# Sheet1.net
KiCad netlist of a schematic drawn in Altium Designer
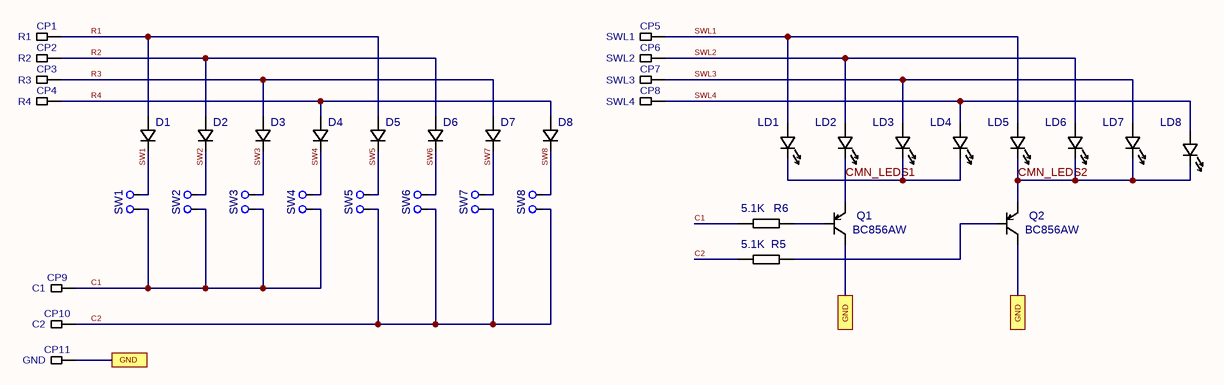
[diagram p0: Sheet1.SCHDOC]

(export (version "E")
  (design (tool "Eeschema 10.0.6"))
  (components
    (comp (ref "CP1")
      (value "R1")
      (footprint "PAD_RRX60Y60D0T")
      (description "PAD_RRX60Y60D0T")
      (libsource (lib "*") (part "PAD_RRX60Y60D0T"))
    )
    (comp (ref "CP2")
      (value "R2")
      (footprint "PAD_RRX60Y60D0T")
      (description "PAD_RRX60Y60D0T")
      (libsource (lib "*") (part "PAD_RRX60Y60D0T"))
    )
    (comp (ref "CP3")
      (value "R3")
      (footprint "PAD_RRX60Y60D0T")
      (description "PAD_RRX60Y60D0T")
      (libsource (lib "*") (part "PAD_RRX60Y60D0T"))
    )
    (comp (ref "CP4")
      (value "R4")
      (footprint "PAD_RRX60Y60D0T")
      (description "PAD_RRX60Y60D0T")
      (libsource (lib "*") (part "PAD_RRX60Y60D0T"))
    )
    (comp (ref "CP5")
      (value "SWL1")
      (footprint "PAD_RRX60Y60D0T")
      (description "PAD_RRX60Y60D0T")
      (libsource (lib "*") (part "PAD_RRX60Y60D0T"))
    )
    (comp (ref "CP6")
      (value "SWL2")
      (footprint "PAD_RRX60Y60D0T")
      (description "PAD_RRX60Y60D0T")
      (libsource (lib "*") (part "PAD_RRX60Y60D0T"))
    )
    (comp (ref "CP7")
      (value "SWL3")
      (footprint "PAD_RRX60Y60D0T")
      (description "PAD_RRX60Y60D0T")
      (libsource (lib "*") (part "PAD_RRX60Y60D0T"))
    )
    (comp (ref "CP8")
      (value "SWL4")
      (footprint "PAD_RRX60Y60D0T")
      (description "PAD_RRX60Y60D0T")
      (libsource (lib "*") (part "PAD_RRX60Y60D0T"))
    )
    (comp (ref "CP9")
      (value "C1")
      (footprint "PAD_RRX60Y60D0T")
      (description "PAD_RRX60Y60D0T")
      (libsource (lib "*") (part "PAD_RRX60Y60D0T"))
    )
    (comp (ref "CP10")
      (value "C2")
      (footprint "PAD_RRX60Y60D0T")
      (description "PAD_RRX60Y60D0T")
      (libsource (lib "*") (part "PAD_RRX60Y60D0T"))
    )
    (comp (ref "CP11")
      (value "GND")
      (footprint "PAD_RRX60Y60D0T")
      (description "PAD_RRX60Y60D0T")
      (libsource (lib "*") (part "PAD_RRX60Y60D0T"))
    )
    (comp (ref "D1") (value "1N4148") (footprint "SOD80") (libsource (lib "*") (part "1N4148")))
    (comp (ref "D2") (value "1N4148") (footprint "SOD80") (libsource (lib "*") (part "1N4148")))
    (comp (ref "D3") (value "1N4148") (footprint "SOD80") (libsource (lib "*") (part "1N4148")))
    (comp (ref "D4") (value "1N4148") (footprint "SOD80") (libsource (lib "*") (part "1N4148")))
    (comp (ref "D5") (value "1N4148") (footprint "SOD80") (libsource (lib "*") (part "1N4148")))
    (comp (ref "D6") (value "1N4148") (footprint "SOD80") (libsource (lib "*") (part "1N4148")))
    (comp (ref "D7") (value "1N4148") (footprint "SOD80") (libsource (lib "*") (part "1N4148")))
    (comp (ref "D8") (value "1N4148") (footprint "SOD80") (libsource (lib "*") (part "1N4148")))
    (comp (ref "LD1") (value "LED_3MM") (footprint "LED_3MM_DIP") (libsource (lib "*") (part "LED_3MM")))
    (comp (ref "LD2") (value "LED_3MM") (footprint "LED_3MM_DIP") (libsource (lib "*") (part "LED_3MM")))
    (comp (ref "LD3") (value "LED_3MM") (footprint "LED_3MM_DIP") (libsource (lib "*") (part "LED_3MM")))
    (comp (ref "LD4") (value "LED_3MM") (footprint "LED_3MM_DIP") (libsource (lib "*") (part "LED_3MM")))
    (comp (ref "LD5") (value "LED_3MM") (footprint "LED_3MM_DIP") (libsource (lib "*") (part "LED_3MM")))
    (comp (ref "LD6") (value "LED_3MM") (footprint "LED_3MM_DIP") (libsource (lib "*") (part "LED_3MM")))
    (comp (ref "LD7") (value "LED_3MM") (footprint "LED_3MM_DIP") (libsource (lib "*") (part "LED_3MM")))
    (comp (ref "LD8") (value "LED_3MM") (footprint "LED_3MM_DIP") (libsource (lib "*") (part "LED_3MM")))
    (comp (ref "Q1") (value "BC856AW") (footprint "SOT23") (libsource (lib "*") (part "BC856AW")))
    (comp (ref "Q2") (value "BC856AW") (footprint "SOT23") (libsource (lib "*") (part "BC856AW")))
    (comp (ref "R5")
      (value "5.1K")
      (footprint "R0805")
      (description "RES_SMD_0805")
      (libsource (lib "*") (part "RES_SMD_0805"))
    )
    (comp (ref "R6")
      (value "5.1K")
      (footprint "R0805")
      (description "RES_SMD_0805")
      (libsource (lib "*") (part "RES_SMD_0805"))
    )
    (comp (ref "SW1")
      (value "2P:EX60Y60D0T-CD100")
      (footprint "2P:EX60Y60D0T-CD100")
      (libsource (lib "*") (part "2P{colon}EX60Y60D0T-CD100"))
    )
    (comp (ref "SW2")
      (value "2P:EX60Y60D0T-CD100")
      (footprint "2P:EX60Y60D0T-CD100")
      (libsource (lib "*") (part "2P{colon}EX60Y60D0T-CD100"))
    )
    (comp (ref "SW3")
      (value "2P:EX60Y60D0T-CD100")
      (footprint "2P:EX60Y60D0T-CD100")
      (libsource (lib "*") (part "2P{colon}EX60Y60D0T-CD100"))
    )
    (comp (ref "SW4")
      (value "2P:EX60Y60D0T-CD100")
      (footprint "2P:EX60Y60D0T-CD100")
      (libsource (lib "*") (part "2P{colon}EX60Y60D0T-CD100"))
    )
    (comp (ref "SW5")
      (value "2P:EX60Y60D0T-CD100")
      (footprint "2P:EX60Y60D0T-CD100")
      (libsource (lib "*") (part "2P{colon}EX60Y60D0T-CD100"))
    )
    (comp (ref "SW6")
      (value "2P:EX60Y60D0T-CD100")
      (footprint "2P:EX60Y60D0T-CD100")
      (libsource (lib "*") (part "2P{colon}EX60Y60D0T-CD100"))
    )
    (comp (ref "SW7")
      (value "2P:EX60Y60D0T-CD100")
      (footprint "2P:EX60Y60D0T-CD100")
      (libsource (lib "*") (part "2P{colon}EX60Y60D0T-CD100"))
    )
    (comp (ref "SW8")
      (value "2P:EX60Y60D0T-CD100")
      (footprint "2P:EX60Y60D0T-CD100")
      (libsource (lib "*") (part "2P{colon}EX60Y60D0T-CD100"))
    )
  )
  (nets
    (net (code "1") (name "/C1") (class "Default")
      (node (ref "CP9") (pin "1") (pintype "passive"))
      (node (ref "R6") (pin "1") (pintype "passive"))
      (node (ref "SW1") (pin "2") (pintype "passive"))
      (node (ref "SW2") (pin "2") (pintype "passive"))
      (node (ref "SW3") (pin "2") (pintype "passive"))
      (node (ref "SW4") (pin "2") (pintype "passive"))
    )
    (net (code "2") (name "/C2") (class "Default")
      (node (ref "CP10") (pin "1") (pintype "passive"))
      (node (ref "R5") (pin "1") (pintype "passive"))
      (node (ref "SW5") (pin "2") (pintype "passive"))
      (node (ref "SW6") (pin "2") (pintype "passive"))
      (node (ref "SW7") (pin "2") (pintype "passive"))
      (node (ref "SW8") (pin "2") (pintype "passive"))
    )
    (net (code "3") (name "/CMN_LEDS1") (class "Default")
      (node (ref "LD1") (pin "K") (pinfunction "K_K") (pintype "passive"))
      (node (ref "LD2") (pin "K") (pinfunction "K_K") (pintype "passive"))
      (node (ref "LD3") (pin "K") (pinfunction "K_K") (pintype "passive"))
      (node (ref "LD4") (pin "K") (pinfunction "K_K") (pintype "passive"))
      (node (ref "Q1") (pin "2") (pinfunction "E_2") (pintype "passive"))
    )
    (net (code "4") (name "/CMN_LEDS2") (class "Default")
      (node (ref "LD5") (pin "K") (pinfunction "K_K") (pintype "passive"))
      (node (ref "LD6") (pin "K") (pinfunction "K_K") (pintype "passive"))
      (node (ref "LD7") (pin "K") (pinfunction "K_K") (pintype "passive"))
      (node (ref "LD8") (pin "K") (pinfunction "K_K") (pintype "passive"))
      (node (ref "Q2") (pin "2") (pinfunction "E_2") (pintype "passive"))
    )
    (net (code "5") (name "/GND") (class "Default")
      (node (ref "CP11") (pin "1") (pintype "passive"))
      (node (ref "Q1") (pin "3") (pinfunction "C_3") (pintype "passive"))
      (node (ref "Q2") (pin "3") (pinfunction "C_3") (pintype "passive"))
    )
    (net (code "6") (name "/R1") (class "Default")
      (node (ref "CP1") (pin "1") (pintype "passive"))
      (node (ref "D1") (pin "A") (pinfunction "A_A") (pintype "passive"))
      (node (ref "D5") (pin "A") (pinfunction "A_A") (pintype "passive"))
    )
    (net (code "7") (name "/R2") (class "Default")
      (node (ref "CP2") (pin "1") (pintype "passive"))
      (node (ref "D2") (pin "A") (pinfunction "A_A") (pintype "passive"))
      (node (ref "D6") (pin "A") (pinfunction "A_A") (pintype "passive"))
    )
    (net (code "8") (name "/R3") (class "Default")
      (node (ref "CP3") (pin "1") (pintype "passive"))
      (node (ref "D3") (pin "A") (pinfunction "A_A") (pintype "passive"))
      (node (ref "D7") (pin "A") (pinfunction "A_A") (pintype "passive"))
    )
    (net (code "9") (name "/R4") (class "Default")
      (node (ref "CP4") (pin "1") (pintype "passive"))
      (node (ref "D4") (pin "A") (pinfunction "A_A") (pintype "passive"))
      (node (ref "D8") (pin "A") (pinfunction "A_A") (pintype "passive"))
    )
    (net (code "10") (name "/SW1") (class "Default")
      (node (ref "D1") (pin "K") (pinfunction "K_K") (pintype "passive"))
      (node (ref "SW1") (pin "1") (pintype "passive"))
    )
    (net (code "11") (name "/SW2") (class "Default")
      (node (ref "D2") (pin "K") (pinfunction "K_K") (pintype "passive"))
      (node (ref "SW2") (pin "1") (pintype "passive"))
    )
    (net (code "12") (name "/SW3") (class "Default")
      (node (ref "D3") (pin "K") (pinfunction "K_K") (pintype "passive"))
      (node (ref "SW3") (pin "1") (pintype "passive"))
    )
    (net (code "13") (name "/SW4") (class "Default")
      (node (ref "D4") (pin "K") (pinfunction "K_K") (pintype "passive"))
      (node (ref "SW4") (pin "1") (pintype "passive"))
    )
    (net (code "14") (name "/SW5") (class "Default")
      (node (ref "D5") (pin "K") (pinfunction "K_K") (pintype "passive"))
      (node (ref "SW5") (pin "1") (pintype "passive"))
    )
    (net (code "15") (name "/SW6") (class "Default")
      (node (ref "D6") (pin "K") (pinfunction "K_K") (pintype "passive"))
      (node (ref "SW6") (pin "1") (pintype "passive"))
    )
    (net (code "16") (name "/SW7") (class "Default")
      (node (ref "D7") (pin "K") (pinfunction "K_K") (pintype "passive"))
      (node (ref "SW7") (pin "1") (pintype "passive"))
    )
    (net (code "17") (name "/SW8") (class "Default")
      (node (ref "D8") (pin "K") (pinfunction "K_K") (pintype "passive"))
      (node (ref "SW8") (pin "1") (pintype "passive"))
    )
    (net (code "18") (name "/SWL1") (class "Default")
      (node (ref "CP5") (pin "1") (pintype "passive"))
      (node (ref "LD1") (pin "A") (pinfunction "A_A") (pintype "passive"))
      (node (ref "LD5") (pin "A") (pinfunction "A_A") (pintype "passive"))
    )
    (net (code "19") (name "/SWL2") (class "Default")
      (node (ref "CP6") (pin "1") (pintype "passive"))
      (node (ref "LD2") (pin "A") (pinfunction "A_A") (pintype "passive"))
      (node (ref "LD6") (pin "A") (pinfunction "A_A") (pintype "passive"))
    )
    (net (code "20") (name "/SWL3") (class "Default")
      (node (ref "CP7") (pin "1") (pintype "passive"))
      (node (ref "LD3") (pin "A") (pinfunction "A_A") (pintype "passive"))
      (node (ref "LD7") (pin "A") (pinfunction "A_A") (pintype "passive"))
    )
    (net (code "21") (name "/SWL4") (class "Default")
      (node (ref "CP8") (pin "1") (pintype "passive"))
      (node (ref "LD4") (pin "A") (pinfunction "A_A") (pintype "passive"))
      (node (ref "LD8") (pin "A") (pinfunction "A_A") (pintype "passive"))
    )
    (net (code "22") (name "Net-(Q1-B)") (class "Default")
      (node (ref "Q1") (pin "1") (pinfunction "B_1") (pintype "passive"))
      (node (ref "R6") (pin "2") (pintype "passive"))
    )
    (net (code "23") (name "Net-(Q2-B)") (class "Default")
      (node (ref "Q2") (pin "1") (pinfunction "B_1") (pintype "passive"))
      (node (ref "R5") (pin "2") (pintype "passive"))
    )
  )
)
